# OpenBookReaderv59.net
KiCad netlist of a schematic drawn in EAGLE
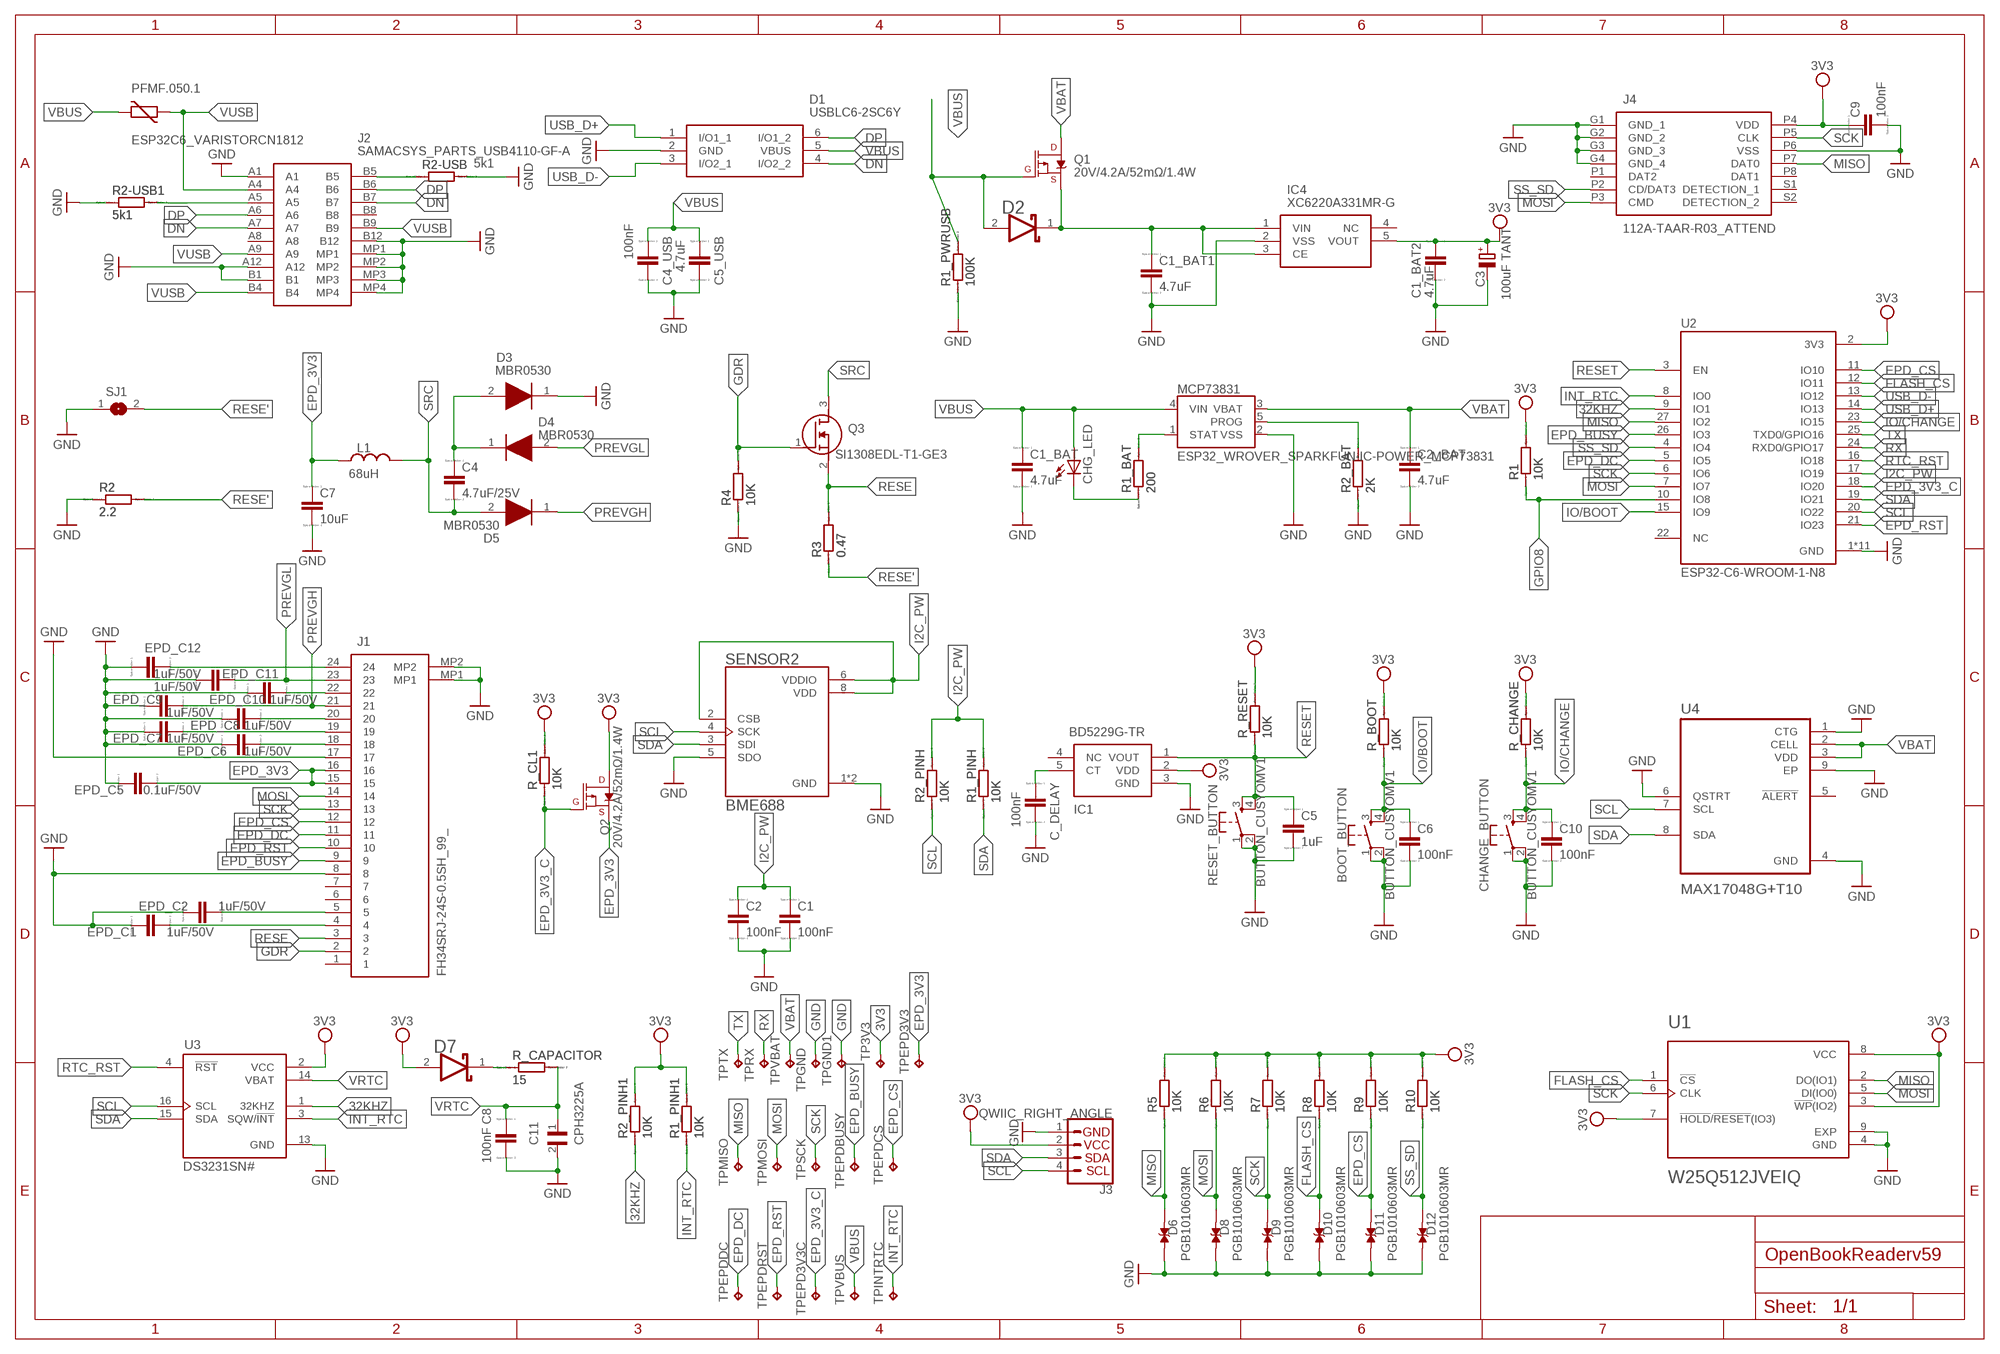
[diagram p0: schematic, sheet 1]

(export (version "E")
  (design (tool "Eeschema 10.0.6"))
  (components
    (comp (ref "BOOT_BUTTON")
      (value "BUTTON_CUSYOMV1")
      (footprint "eagle-import:MYBUTTON")
      (libsource (lib "eagle-import") (part "BUTTON_CUSYOMV1"))
    )
    (comp (ref "C1")
      (value "100nF")
      (footprint "eagle-import:EAGLE-LTSPICE_C0402")
      (libsource (lib "eagle-import") (part "EAGLE-LTSPICE_CC0402"))
    )
    (comp (ref "C1_BAT")
      (value "4.7uF")
      (footprint "eagle-import:EAGLE-LTSPICE_C0402")
      (libsource (lib "eagle-import") (part "EAGLE-LTSPICE_CC0402"))
    )
    (comp (ref "C1_BAT1")
      (value "4.7uF")
      (footprint "eagle-import:EAGLE-LTSPICE_C0402")
      (libsource (lib "eagle-import") (part "EAGLE-LTSPICE_CC0402"))
    )
    (comp (ref "C1_BAT2")
      (value "4.7uF")
      (footprint "eagle-import:EAGLE-LTSPICE_C0402")
      (libsource (lib "eagle-import") (part "EAGLE-LTSPICE_CC0402"))
    )
    (comp (ref "C2")
      (value "100nF")
      (footprint "eagle-import:EAGLE-LTSPICE_C0402")
      (libsource (lib "eagle-import") (part "EAGLE-LTSPICE_CC0402"))
    )
    (comp (ref "C2_BAT")
      (value "4.7uF")
      (footprint "eagle-import:EAGLE-LTSPICE_C0402")
      (libsource (lib "eagle-import") (part "EAGLE-LTSPICE_CC0402"))
    )
    (comp (ref "C3")
      (value "100uF TANT")
      (footprint "eagle-import:RCL_CT3528")
      (libsource (lib "eagle-import") (part "RCL_CPOL-EUCT3528"))
    )
    (comp (ref "C4")
      (value "4.7uF/25V")
      (footprint "eagle-import:EAGLE-LTSPICE_C0402")
      (libsource (lib "eagle-import") (part "EAGLE-LTSPICE_CC0402"))
    )
    (comp (ref "C4_USB")
      (value "100nF")
      (footprint "eagle-import:EAGLE-LTSPICE_C0402")
      (libsource (lib "eagle-import") (part "EAGLE-LTSPICE_CC0402"))
    )
    (comp (ref "C5")
      (value "1uF")
      (footprint "eagle-import:EAGLE-LTSPICE_C0402")
      (libsource (lib "eagle-import") (part "EAGLE-LTSPICE_CC0402"))
    )
    (comp (ref "C5_USB")
      (value "4.7uF")
      (footprint "eagle-import:EAGLE-LTSPICE_C0402")
      (libsource (lib "eagle-import") (part "EAGLE-LTSPICE_CC0402"))
    )
    (comp (ref "C6")
      (value "100nF")
      (footprint "eagle-import:EAGLE-LTSPICE_C0402")
      (libsource (lib "eagle-import") (part "EAGLE-LTSPICE_CC0402"))
    )
    (comp (ref "C7")
      (value "10uF")
      (footprint "eagle-import:EAGLE-LTSPICE_C0402")
      (libsource (lib "eagle-import") (part "EAGLE-LTSPICE_CC0402"))
    )
    (comp (ref "C8")
      (value "100nF")
      (footprint "eagle-import:EAGLE-LTSPICE_C0402")
      (libsource (lib "eagle-import") (part "EAGLE-LTSPICE_CC0402"))
    )
    (comp (ref "C9")
      (value "100nF")
      (footprint "eagle-import:EAGLE-LTSPICE_C0402")
      (libsource (lib "eagle-import") (part "EAGLE-LTSPICE_CC0402"))
    )
    (comp (ref "C10")
      (value "100nF")
      (footprint "eagle-import:EAGLE-LTSPICE_C0402")
      (libsource (lib "eagle-import") (part "EAGLE-LTSPICE_CC0402"))
    )
    (comp (ref "C11")
      (value "CPH3225A")
      (footprint "eagle-import:CAPCP3225X100N")
      (fields (field (name "MF") "Seiko Instruments"))
      (libsource (lib "eagle-import") (part "CPH3225A"))
    )
    (comp (ref "CHANGE_BUTTON")
      (value "BUTTON_CUSYOMV1")
      (footprint "eagle-import:MYBUTTON")
      (libsource (lib "eagle-import") (part "BUTTON_CUSYOMV1"))
    )
    (comp (ref "CHG_LED")
      (value "ADAFRUIT_LEDCHIP-LED0603")
      (footprint "eagle-import:ADAFRUIT_CHIP-LED0603")
      (libsource (lib "eagle-import") (part "ADAFRUIT_LEDCHIP-LED0603"))
    )
    (comp (ref "C_DELAY")
      (value "100nF")
      (footprint "eagle-import:EAGLE-LTSPICE_C0402")
      (libsource (lib "eagle-import") (part "EAGLE-LTSPICE_CC0402"))
    )
    (comp (ref "D1")
      (value "USBLC6-2SC6Y")
      (footprint "eagle-import:SOT95P280X145-6N")
      (fields (field (name "MF") "STMicroelectronics"))
      (libsource (lib "eagle-import") (part "USBLC6-2SC6Y"))
    )
    (comp (ref "D2")
      (value "ESP32_WROVER_AVX---SD0805S020S1R0_AVX_SD0805S020S1R0_0_0AVX_SD0805S020S1R0_0_0")
      (footprint "eagle-import:ESP32_WROVER_AVX---SD0805S020S1R0_AVX_SD0805S020S1R0_0")
      (fields
        (field (name "DIGIKEY_PART_NUMBER") "478-7800-1-ND")
        (field (name "MF") "AVX")
        (field (name "MOUSER_PART_NUMBER") "581-SD0805S020S1R0")
      )
      (libsource (lib "eagle-import") (part "ESP32_WROVER_AVX---SD0805S020S1R0_AVX_SD0805S020S1R0_0_0AVX_SD0805S020S1R0_0_0"))
    )
    (comp (ref "D3")
      (value "MBR0530")
      (footprint "eagle-import:SOD3716X135N")
      (fields (field (name "MF") "ON Semiconductor"))
      (libsource (lib "eagle-import") (part "MBR0530"))
    )
    (comp (ref "D4")
      (value "MBR0530")
      (footprint "eagle-import:SOD3716X135N")
      (fields (field (name "MF") "ON Semiconductor"))
      (libsource (lib "eagle-import") (part "MBR0530"))
    )
    (comp (ref "D5")
      (value "MBR0530")
      (footprint "eagle-import:SOD3716X135N")
      (fields (field (name "MF") "ON Semiconductor"))
      (libsource (lib "eagle-import") (part "MBR0530"))
    )
    (comp (ref "D6")
      (value "PGB1010603MR")
      (footprint "eagle-import:DIOC1608X36N")
      (fields (field (name "MF") "Littelfuse Inc."))
      (libsource (lib "eagle-import") (part "PGB1010603MR"))
    )
    (comp (ref "D7")
      (value "ESP32_WROVER_AVX---SD0805S020S1R0_AVX_SD0805S020S1R0_0_0AVX_SD0805S020S1R0_0_0")
      (footprint "eagle-import:ESP32_WROVER_AVX---SD0805S020S1R0_AVX_SD0805S020S1R0_0")
      (fields
        (field (name "DIGIKEY_PART_NUMBER") "478-7800-1-ND")
        (field (name "MF") "AVX")
        (field (name "MOUSER_PART_NUMBER") "581-SD0805S020S1R0")
      )
      (libsource (lib "eagle-import") (part "ESP32_WROVER_AVX---SD0805S020S1R0_AVX_SD0805S020S1R0_0_0AVX_SD0805S020S1R0_0_0"))
    )
    (comp (ref "D8")
      (value "PGB1010603MR")
      (footprint "eagle-import:DIOC1608X36N")
      (fields (field (name "MF") "Littelfuse Inc."))
      (libsource (lib "eagle-import") (part "PGB1010603MR"))
    )
    (comp (ref "D9")
      (value "PGB1010603MR")
      (footprint "eagle-import:DIOC1608X36N")
      (fields (field (name "MF") "Littelfuse Inc."))
      (libsource (lib "eagle-import") (part "PGB1010603MR"))
    )
    (comp (ref "D10")
      (value "PGB1010603MR")
      (footprint "eagle-import:DIOC1608X36N")
      (fields (field (name "MF") "Littelfuse Inc."))
      (libsource (lib "eagle-import") (part "PGB1010603MR"))
    )
    (comp (ref "D11")
      (value "PGB1010603MR")
      (footprint "eagle-import:DIOC1608X36N")
      (fields (field (name "MF") "Littelfuse Inc."))
      (libsource (lib "eagle-import") (part "PGB1010603MR"))
    )
    (comp (ref "D12")
      (value "PGB1010603MR")
      (footprint "eagle-import:DIOC1608X36N")
      (fields (field (name "MF") "Littelfuse Inc."))
      (libsource (lib "eagle-import") (part "PGB1010603MR"))
    )
    (comp (ref "EPD_C1")
      (value "1uF/50V")
      (footprint "eagle-import:EAGLE-LTSPICE_C0402")
      (libsource (lib "eagle-import") (part "EAGLE-LTSPICE_CC0402"))
    )
    (comp (ref "EPD_C2")
      (value "1uF/50V")
      (footprint "eagle-import:EAGLE-LTSPICE_C0402")
      (libsource (lib "eagle-import") (part "EAGLE-LTSPICE_CC0402"))
    )
    (comp (ref "EPD_C5")
      (value "0.1uF/50V")
      (footprint "eagle-import:EAGLE-LTSPICE_C0402")
      (libsource (lib "eagle-import") (part "EAGLE-LTSPICE_CC0402"))
    )
    (comp (ref "EPD_C6")
      (value "1uF/50V")
      (footprint "eagle-import:EAGLE-LTSPICE_C0402")
      (libsource (lib "eagle-import") (part "EAGLE-LTSPICE_CC0402"))
    )
    (comp (ref "EPD_C7")
      (value "1uF/50V")
      (footprint "eagle-import:EAGLE-LTSPICE_C0402")
      (libsource (lib "eagle-import") (part "EAGLE-LTSPICE_CC0402"))
    )
    (comp (ref "EPD_C8")
      (value "1uF/50V")
      (footprint "eagle-import:EAGLE-LTSPICE_C0402")
      (libsource (lib "eagle-import") (part "EAGLE-LTSPICE_CC0402"))
    )
    (comp (ref "EPD_C9")
      (value "1uF/50V")
      (footprint "eagle-import:EAGLE-LTSPICE_C0402")
      (libsource (lib "eagle-import") (part "EAGLE-LTSPICE_CC0402"))
    )
    (comp (ref "EPD_C10")
      (value "1uF/50V")
      (footprint "eagle-import:EAGLE-LTSPICE_C0402")
      (libsource (lib "eagle-import") (part "EAGLE-LTSPICE_CC0402"))
    )
    (comp (ref "EPD_C11")
      (value "1uF/50V")
      (footprint "eagle-import:EAGLE-LTSPICE_C0402")
      (libsource (lib "eagle-import") (part "EAGLE-LTSPICE_CC0402"))
    )
    (comp (ref "EPD_C12")
      (value "1uF/50V")
      (footprint "eagle-import:EAGLE-LTSPICE_C0402")
      (libsource (lib "eagle-import") (part "EAGLE-LTSPICE_CC0402"))
    )
    (comp (ref "IC1")
      (value "BD5229G-TR")
      (footprint "eagle-import:SOT95P280X125-5N")
      (fields (field (name "MOUSER_PART_NUMBER") "755-BD5229G-TR"))
      (libsource (lib "eagle-import") (part "BD5229G-TR"))
    )
    (comp (ref "IC4")
      (value "XC6220A331MR-G")
      (footprint "eagle-import:SOT95P280X120-5N")
      (fields (field (name "MOUSER_PART_NUMBER") "865-XC6220A331MR-G"))
      (libsource (lib "eagle-import") (part "XC6220A331MR-G"))
    )
    (comp (ref "J1")
      (value "FH34SRJ-24S-0.5SH_99_")
      (footprint "eagle-import:FH34SRJ24S05SH99")
      (fields
        (field (name "MANUFACTURER_PART_NUMBER") "FH34SRJ-24S-0.5SH(99)")
        (field (name "MOUSER_PART_NUMBER") "798-FH34SRJ24S05SH99")
      )
      (libsource (lib "eagle-import") (part "FH34SRJ-24S-0.5SH_99_"))
    )
    (comp (ref "J2")
      (value "SAMACSYS_PARTS_USB4110-GF-A")
      (footprint "eagle-import:SAMACSYS_PARTS_USB4110GFA")
      (fields
        (field (name "MANUFACTURER_PART_NUMBER") "USB4110-GF-A")
        (field (name "MOUSER_PART_NUMBER") "640-USB4110-GF-A")
      )
      (libsource (lib "eagle-import") (part "SAMACSYS_PARTS_USB4110-GF-A"))
    )
    (comp (ref "J3")
      (value "QWIIC_RIGHT_ANGLE")
      (footprint "eagle-import:JST04_1MM_RA")
      (libsource (lib "eagle-import") (part "QWIIC_CONNECTORJS-1MM"))
    )
    (comp (ref "J4")
      (value "112A-TAAR-R03_ATTEND")
      (footprint "eagle-import:112ATAARR03ATTEND")
      (fields (field (name "MANUFACTURER_PART_NUMBER") "112A-TAAR-R03 ATTEND"))
      (libsource (lib "eagle-import") (part "112A-TAAR-R03_ATTEND"))
    )
    (comp (ref "L1")
      (value "68uH")
      (footprint "eagle-import:INDC1006X60N")
      (libsource (lib "eagle-import") (part "INDUCTORCHIP-0402(1006-METRIC)_"))
    )
    (comp (ref "MCP73831")
      (value "ESP32_WROVER_SPARKFUN-IC-POWER_MCP73831")
      (footprint "eagle-import:ESP32_WROVER_SPARKFUN-IC-POWER_SOT23-5")
      (libsource (lib "eagle-import") (part "ESP32_WROVER_SPARKFUN-IC-POWER_MCP73831"))
    )
    (comp (ref "PFMF.050.1")
      (value "ESP32C6_VARISTORCN1812")
      (footprint "eagle-import:ESP32C6_VARISTOR_CT_CN1812")
      (libsource (lib "eagle-import") (part "ESP32C6_VARISTORCN1812"))
    )
    (comp (ref "Q1")
      (value "20V/4.2A/52mΩ/1.4W")
      (footprint "eagle-import:ESP32_WROVER_SPARKFUN-DISCRETESEMI_SOT23-3")
      (libsource (lib "eagle-import") (part "ESP32_WROVER_SPARKFUN-DISCRETESEMI_MOSFET_PCH-DMG2305UX-7"))
    )
    (comp (ref "Q2")
      (value "20V/4.2A/52mΩ/1.4W")
      (footprint "eagle-import:ESP32_WROVER_SPARKFUN-DISCRETESEMI_SOT23-3")
      (libsource (lib "eagle-import") (part "ESP32_WROVER_SPARKFUN-DISCRETESEMI_MOSFET_PCH-DMG2305UX-7"))
    )
    (comp (ref "Q3")
      (value "SI1308EDL-T1-GE3")
      (footprint "eagle-import:SOT65P210X110-3N")
      (fields (field (name "MF") "Vishay Siliconix"))
      (libsource (lib "eagle-import") (part "SI1308EDL-T1-GE3"))
    )
    (comp (ref "R1")
      (value "10K")
      (footprint "eagle-import:ESP32_WROVER_EAGLE-LTSPICE_R0402")
      (libsource (lib "eagle-import") (part "ESP32_WROVER_EAGLE-LTSPICE_RR0402"))
    )
    (comp (ref "R1_BAT")
      (value "200")
      (footprint "eagle-import:ESP32_WROVER_EAGLE-LTSPICE_R0402")
      (libsource (lib "eagle-import") (part "ESP32_WROVER_EAGLE-LTSPICE_RR0402"))
    )
    (comp (ref "R1_PINH")
      (value "10K")
      (footprint "eagle-import:ESP32_WROVER_EAGLE-LTSPICE_R0402")
      (libsource (lib "eagle-import") (part "ESP32_WROVER_EAGLE-LTSPICE_RR0402"))
    )
    (comp (ref "R1_PINH1")
      (value "10K")
      (footprint "eagle-import:ESP32_WROVER_EAGLE-LTSPICE_R0402")
      (libsource (lib "eagle-import") (part "ESP32_WROVER_EAGLE-LTSPICE_RR0402"))
    )
    (comp (ref "R1_PWRUSB")
      (value "100K")
      (footprint "eagle-import:ESP32_WROVER_EAGLE-LTSPICE_R0402")
      (libsource (lib "eagle-import") (part "ESP32_WROVER_EAGLE-LTSPICE_RR0402"))
    )
    (comp (ref "R2")
      (value "2.2")
      (footprint "eagle-import:ESP32_WROVER_EAGLE-LTSPICE_R0402")
      (libsource (lib "eagle-import") (part "ESP32_WROVER_EAGLE-LTSPICE_RR0402"))
    )
    (comp (ref "R2-USB")
      (value "5k1")
      (footprint "eagle-import:ESP32_WROVER_EAGLE-LTSPICE_R0402")
      (libsource (lib "eagle-import") (part "ESP32_WROVER_EAGLE-LTSPICE_RR0402"))
    )
    (comp (ref "R2-USB1")
      (value "5k1")
      (footprint "eagle-import:ESP32_WROVER_EAGLE-LTSPICE_R0402")
      (libsource (lib "eagle-import") (part "ESP32_WROVER_EAGLE-LTSPICE_RR0402"))
    )
    (comp (ref "R2_BAT")
      (value "2K")
      (footprint "eagle-import:ESP32_WROVER_EAGLE-LTSPICE_R0402")
      (libsource (lib "eagle-import") (part "ESP32_WROVER_EAGLE-LTSPICE_RR0402"))
    )
    (comp (ref "R2_PINH")
      (value "10K")
      (footprint "eagle-import:ESP32_WROVER_EAGLE-LTSPICE_R0402")
      (libsource (lib "eagle-import") (part "ESP32_WROVER_EAGLE-LTSPICE_RR0402"))
    )
    (comp (ref "R2_PINH1")
      (value "10K")
      (footprint "eagle-import:ESP32_WROVER_EAGLE-LTSPICE_R0402")
      (libsource (lib "eagle-import") (part "ESP32_WROVER_EAGLE-LTSPICE_RR0402"))
    )
    (comp (ref "R3")
      (value "0.47")
      (footprint "eagle-import:ESP32_WROVER_EAGLE-LTSPICE_R0402")
      (libsource (lib "eagle-import") (part "ESP32_WROVER_EAGLE-LTSPICE_RR0402"))
    )
    (comp (ref "R4")
      (value "10K")
      (footprint "eagle-import:ESP32_WROVER_EAGLE-LTSPICE_R0402")
      (libsource (lib "eagle-import") (part "ESP32_WROVER_EAGLE-LTSPICE_RR0402"))
    )
    (comp (ref "R5")
      (value "10K")
      (footprint "eagle-import:ESP32_WROVER_EAGLE-LTSPICE_R0402")
      (libsource (lib "eagle-import") (part "ESP32_WROVER_EAGLE-LTSPICE_RR0402"))
    )
    (comp (ref "R6")
      (value "10K")
      (footprint "eagle-import:ESP32_WROVER_EAGLE-LTSPICE_R0402")
      (libsource (lib "eagle-import") (part "ESP32_WROVER_EAGLE-LTSPICE_RR0402"))
    )
    (comp (ref "R7")
      (value "10K")
      (footprint "eagle-import:ESP32_WROVER_EAGLE-LTSPICE_R0402")
      (libsource (lib "eagle-import") (part "ESP32_WROVER_EAGLE-LTSPICE_RR0402"))
    )
    (comp (ref "R8")
      (value "10K")
      (footprint "eagle-import:ESP32_WROVER_EAGLE-LTSPICE_R0402")
      (libsource (lib "eagle-import") (part "ESP32_WROVER_EAGLE-LTSPICE_RR0402"))
    )
    (comp (ref "R9")
      (value "10K")
      (footprint "eagle-import:ESP32_WROVER_EAGLE-LTSPICE_R0402")
      (libsource (lib "eagle-import") (part "ESP32_WROVER_EAGLE-LTSPICE_RR0402"))
    )
    (comp (ref "R10")
      (value "10K")
      (footprint "eagle-import:ESP32_WROVER_EAGLE-LTSPICE_R0402")
      (libsource (lib "eagle-import") (part "ESP32_WROVER_EAGLE-LTSPICE_RR0402"))
    )
    (comp (ref "RESET_BUTTON")
      (value "BUTTON_CUSYOMV1")
      (footprint "eagle-import:MYBUTTON")
      (libsource (lib "eagle-import") (part "BUTTON_CUSYOMV1"))
    )
    (comp (ref "R_BOOT")
      (value "10K")
      (footprint "eagle-import:ESP32_WROVER_EAGLE-LTSPICE_R0402")
      (libsource (lib "eagle-import") (part "ESP32_WROVER_EAGLE-LTSPICE_RR0402"))
    )
    (comp (ref "R_CAPACITOR")
      (value "15")
      (footprint "eagle-import:ESP32_WROVER_EAGLE-LTSPICE_R0402")
      (libsource (lib "eagle-import") (part "ESP32_WROVER_EAGLE-LTSPICE_RR0402"))
    )
    (comp (ref "R_CHANGE")
      (value "10K")
      (footprint "eagle-import:ESP32_WROVER_EAGLE-LTSPICE_R0402")
      (libsource (lib "eagle-import") (part "ESP32_WROVER_EAGLE-LTSPICE_RR0402"))
    )
    (comp (ref "R_CL1")
      (value "10K")
      (footprint "eagle-import:ESP32_WROVER_EAGLE-LTSPICE_R0402")
      (libsource (lib "eagle-import") (part "ESP32_WROVER_EAGLE-LTSPICE_RR0402"))
    )
    (comp (ref "R_RESET")
      (value "10K")
      (footprint "eagle-import:ESP32_WROVER_EAGLE-LTSPICE_R0402")
      (libsource (lib "eagle-import") (part "ESP32_WROVER_EAGLE-LTSPICE_RR0402"))
    )
    (comp (ref "SENSOR2")
      (value "BME688")
      (footprint "eagle-import:ESP32_WROVER_BME680_PSON80P300X300X100-8N")
      (fields (field (name "MF") "Bosch Sensortec") (field (name "MP") "BME680"))
      (libsource (lib "eagle-import") (part "ESP32_WROVER_BME680_BME680"))
    )
    (comp (ref "SJ1") (value "SJ") (footprint "eagle-import:SJ") (libsource (lib "eagle-import") (part "SJ")))
    (comp (ref "TP3V3")
      (value "TPTP20R")
      (footprint "eagle-import:TP20R")
      (libsource (lib "eagle-import") (part "TPTP20R"))
    )
    (comp (ref "TPEPD3V3")
      (value "TPTP20R")
      (footprint "eagle-import:TP20R")
      (libsource (lib "eagle-import") (part "TPTP20R"))
    )
    (comp (ref "TPEPD3V3C")
      (value "TPTP20R")
      (footprint "eagle-import:TP20R")
      (libsource (lib "eagle-import") (part "TPTP20R"))
    )
    (comp (ref "TPEPDBUSY")
      (value "TPTP20R")
      (footprint "eagle-import:TP20R")
      (libsource (lib "eagle-import") (part "TPTP20R"))
    )
    (comp (ref "TPEPDCS")
      (value "TPTP20R")
      (footprint "eagle-import:TP20R")
      (libsource (lib "eagle-import") (part "TPTP20R"))
    )
    (comp (ref "TPEPDDC")
      (value "TPTP20R")
      (footprint "eagle-import:TP20R")
      (libsource (lib "eagle-import") (part "TPTP20R"))
    )
    (comp (ref "TPEPDRST")
      (value "TPTP20R")
      (footprint "eagle-import:TP20R")
      (libsource (lib "eagle-import") (part "TPTP20R"))
    )
    (comp (ref "TPGND")
      (value "TPTP20R")
      (footprint "eagle-import:TP20R")
      (libsource (lib "eagle-import") (part "TPTP20R"))
    )
    (comp (ref "TPGND1")
      (value "TPTP20R")
      (footprint "eagle-import:TP20R")
      (libsource (lib "eagle-import") (part "TPTP20R"))
    )
    (comp (ref "TPINTRTC")
      (value "TPTP20R")
      (footprint "eagle-import:TP20R")
      (libsource (lib "eagle-import") (part "TPTP20R"))
    )
    (comp (ref "TPMISO")
      (value "TPTP20R")
      (footprint "eagle-import:TP20R")
      (libsource (lib "eagle-import") (part "TPTP20R"))
    )
    (comp (ref "TPMOSI")
      (value "TPTP20R")
      (footprint "eagle-import:TP20R")
      (libsource (lib "eagle-import") (part "TPTP20R"))
    )
    (comp (ref "TPRX")
      (value "TPTP20R")
      (footprint "eagle-import:TP20R")
      (libsource (lib "eagle-import") (part "TPTP20R"))
    )
    (comp (ref "TPSCK")
      (value "TPTP20R")
      (footprint "eagle-import:TP20R")
      (libsource (lib "eagle-import") (part "TPTP20R"))
    )
    (comp (ref "TPTX")
      (value "TPTP20R")
      (footprint "eagle-import:TP20R")
      (libsource (lib "eagle-import") (part "TPTP20R"))
    )
    (comp (ref "TPVBAT")
      (value "TPTP20R")
      (footprint "eagle-import:TP20R")
      (libsource (lib "eagle-import") (part "TPTP20R"))
    )
    (comp (ref "TPVBUS")
      (value "TPTP20R")
      (footprint "eagle-import:TP20R")
      (libsource (lib "eagle-import") (part "TPTP20R"))
    )
    (comp (ref "U1")
      (value "W25Q512JVEIQ")
      (footprint "eagle-import:SON127P600X800X80-9N")
      (fields (field (name "MF") "Winbond Electronics"))
      (libsource (lib "eagle-import") (part "W25Q512JVEIQ"))
    )
    (comp (ref "U2")
      (value "ESP32-C6-WROOM-1-N8")
      (footprint "eagle-import:XCVR_ESP32-C6-WROOM-1-N8")
      (fields (field (name "MF") "Espressif Systems"))
      (libsource (lib "eagle-import") (part "ESP32-C6-WROOM-1-N8"))
    )
    (comp (ref "U3")
      (value "DS3231SN#")
      (footprint "eagle-import:SOIC127P1032X265-16N")
      (fields (field (name "MF") "Analog Devices"))
      (libsource (lib "eagle-import") (part "DS3231SN#"))
    )
    (comp (ref "U4")
      (value "MAX17048G+T10")
      (footprint "eagle-import:SON50P200X200X80-9N")
      (fields (field (name "MF") "Analog Devices"))
      (libsource (lib "eagle-import") (part "MAX17048G+T10"))
    )
  )
  (nets
    (net (code "1") (name "3V3") (class "Default")
      (node (ref "C1_BAT2") (pin "1") (pinfunction "1_1") (pintype "passive"))
      (node (ref "C3") (pin "+") (pinfunction "+_+") (pintype "passive"))
      (node (ref "C9") (pin "1") (pinfunction "1_1") (pintype "passive"))
      (node (ref "D7") (pin "2") (pinfunction "ANODE_2") (pintype "bidirectional"))
      (node (ref "IC1") (pin "2") (pinfunction "VDD_2") (pintype "bidirectional"))
      (node (ref "IC4") (pin "5") (pinfunction "VOUT_5") (pintype "bidirectional"))
      (node (ref "J3") (pin "2") (pinfunction "2_2") (pintype "power_in"))
      (node (ref "J4") (pin "P4") (pinfunction "VDD_P4") (pintype "bidirectional"))
      (node (ref "Q2") (pin "3") (pinfunction "D_3") (pintype "bidirectional"))
      (node (ref "R1") (pin "2") (pinfunction "2_2") (pintype "passive"))
      (node (ref "R10") (pin "2") (pinfunction "2_2") (pintype "passive"))
      (node (ref "R1_PINH1") (pin "2") (pinfunction "2_2") (pintype "passive"))
      (node (ref "R2_PINH1") (pin "2") (pinfunction "2_2") (pintype "passive"))
      (node (ref "R5") (pin "2") (pinfunction "2_2") (pintype "passive"))
      (node (ref "R6") (pin "2") (pinfunction "2_2") (pintype "passive"))
      (node (ref "R7") (pin "2") (pinfunction "2_2") (pintype "passive"))
      (node (ref "R8") (pin "2") (pinfunction "2_2") (pintype "passive"))
      (node (ref "R9") (pin "2") (pinfunction "2_2") (pintype "passive"))
      (node (ref "R_BOOT") (pin "2") (pinfunction "2_2") (pintype "passive"))
      (node (ref "R_CHANGE") (pin "2") (pinfunction "2_2") (pintype "passive"))
      (node (ref "R_CL1") (pin "2") (pinfunction "2_2") (pintype "passive"))
      (node (ref "R_RESET") (pin "2") (pinfunction "2_2") (pintype "passive"))
      (node (ref "TP3V3") (pin "TP") (pinfunction "TP_TP") (pintype "input"))
      (node (ref "U1") (pin "3") (pinfunction "~{WP}(IO2)_3") (pintype "bidirectional"))
      (node (ref "U1") (pin "7") (pinfunction "~{HOLD}/~{RESET}(IO3)_7") (pintype "bidirectional"))
      (node (ref "U1") (pin "8") (pinfunction "VCC_8") (pintype "power_in"))
      (node (ref "U2") (pin "2") (pinfunction "3V3_2") (pintype "power_in"))
      (node (ref "U3") (pin "2") (pinfunction "VCC_2") (pintype "power_in"))
    )
    (net (code "2") (name "32KHZ") (class "Default")
      (node (ref "R2_PINH1") (pin "1") (pinfunction "1_1") (pintype "passive"))
      (node (ref "U2") (pin "9") (pinfunction "IO1_9") (pintype "bidirectional"))
      (node (ref "U3") (pin "1") (pinfunction "32KHZ_1") (pintype "output"))
    )
    (net (code "3") (name "DN") (class "Default")
      (node (ref "D1") (pin "4") (pinfunction "I/O2_2_4") (pintype "bidirectional"))
      (node (ref "J2") (pin "A7") (pinfunction "A7_A7") (pintype "bidirectional"))
      (node (ref "J2") (pin "B7") (pinfunction "B7_B7") (pintype "bidirectional"))
    )
    (net (code "4") (name "DP") (class "Default")
      (node (ref "D1") (pin "6") (pinfunction "I/O1_2_6") (pintype "bidirectional"))
      (node (ref "J2") (pin "A6") (pinfunction "A6_A6") (pintype "bidirectional"))
      (node (ref "J2") (pin "B6") (pinfunction "B6_B6") (pintype "bidirectional"))
    )
    (net (code "5") (name "EPD_3V3") (class "Default")
      (node (ref "C7") (pin "1") (pinfunction "1_1") (pintype "passive"))
      (node (ref "EPD_C5") (pin "2") (pinfunction "2_2") (pintype "passive"))
      (node (ref "J1") (pin "15") (pinfunction "15_15") (pintype "bidirectional"))
      (node (ref "J1") (pin "16") (pinfunction "16_16") (pintype "bidirectional"))
      (node (ref "L1") (pin "1") (pinfunction "1_1") (pintype "passive"))
      (node (ref "Q2") (pin "2") (pinfunction "S_2") (pintype "bidirectional"))
      (node (ref "TPEPD3V3") (pin "TP") (pinfunction "TP_TP") (pintype "input"))
    )
    (net (code "6") (name "EPD_3V3_C") (class "Default")
      (node (ref "Q2") (pin "1") (pinfunction "G_1") (pintype "bidirectional"))
      (node (ref "R_CL1") (pin "1") (pinfunction "1_1") (pintype "passive"))
      (node (ref "TPEPD3V3C") (pin "TP") (pinfunction "TP_TP") (pintype "input"))
      (node (ref "U2") (pin "18") (pinfunction "IO20_18") (pintype "bidirectional"))
    )
    (net (code "7") (name "EPD_BUSY") (class "Default")
      (node (ref "J1") (pin "9") (pinfunction "9_9") (pintype "bidirectional"))
      (node (ref "TPEPDBUSY") (pin "TP") (pinfunction "TP_TP") (pintype "input"))
      (node (ref "U2") (pin "26") (pinfunction "IO3_26") (pintype "bidirectional"))
    )
    (net (code "8") (name "EPD_CS") (class "Default")
      (node (ref "D11") (pin "2") (pinfunction "2_2") (pintype "passive"))
      (node (ref "J1") (pin "12") (pinfunction "12_12") (pintype "bidirectional"))
      (node (ref "R9") (pin "1") (pinfunction "1_1") (pintype "passive"))
      (node (ref "TPEPDCS") (pin "TP") (pinfunction "TP_TP") (pintype "input"))
      (node (ref "U2") (pin "11") (pinfunction "IO10_11") (pintype "bidirectional"))
    )
    (net (code "9") (name "EPD_DC") (class "Default")
      (node (ref "J1") (pin "11") (pinfunction "11_11") (pintype "bidirectional"))
      (node (ref "TPEPDDC") (pin "TP") (pinfunction "TP_TP") (pintype "input"))
      (node (ref "U2") (pin "5") (pinfunction "IO5_5") (pintype "bidirectional"))
    )
    (net (code "10") (name "EPD_RST") (class "Default")
      (node (ref "J1") (pin "10") (pinfunction "10_10") (pintype "bidirectional"))
      (node (ref "TPEPDRST") (pin "TP") (pinfunction "TP_TP") (pintype "input"))
      (node (ref "U2") (pin "21") (pinfunction "IO23_21") (pintype "bidirectional"))
    )
    (net (code "11") (name "FLASH_CS") (class "Default")
      (node (ref "D10") (pin "2") (pinfunction "2_2") (pintype "passive"))
      (node (ref "R8") (pin "1") (pinfunction "1_1") (pintype "passive"))
      (node (ref "U1") (pin "1") (pinfunction "~{CS}_1") (pintype "input"))
      (node (ref "U2") (pin "12") (pinfunction "IO11_12") (pintype "bidirectional"))
    )
    (net (code "12") (name "GDR") (class "Default")
      (node (ref "J1") (pin "2") (pinfunction "2_2") (pintype "bidirectional"))
      (node (ref "Q3") (pin "1") (pinfunction "G_1") (pintype "bidirectional"))
      (node (ref "R4") (pin "2") (pinfunction "2_2") (pintype "passive"))
    )
    (net (code "13") (name "GND") (class "Default")
      (node (ref "BOOT_BUTTON") (pin "1") (pinfunction "1_1") (pintype "passive"))
      (node (ref "BOOT_BUTTON") (pin "2") (pinfunction "2_2") (pintype "passive"))
      (node (ref "C1") (pin "2") (pinfunction "2_2") (pintype "passive"))
      (node (ref "C10") (pin "2") (pinfunction "2_2") (pintype "passive"))
      (node (ref "C11") (pin "2") (pinfunction "2_2") (pintype "passive"))
      (node (ref "C1_BAT") (pin "2") (pinfunction "2_2") (pintype "passive"))
      (node (ref "C1_BAT1") (pin "2") (pinfunction "2_2") (pintype "passive"))
      (node (ref "C1_BAT2") (pin "2") (pinfunction "2_2") (pintype "passive"))
      (node (ref "C2") (pin "2") (pinfunction "2_2") (pintype "passive"))
      (node (ref "C2_BAT") (pin "2") (pinfunction "2_2") (pintype "passive"))
      (node (ref "C3") (pin "-") (pinfunction "-_-") (pintype "passive"))
      (node (ref "C4_USB") (pin "2") (pinfunction "2_2") (pintype "passive"))
      (node (ref "C5") (pin "2") (pinfunction "2_2") (pintype "passive"))
      (node (ref "C5_USB") (pin "2") (pinfunction "2_2") (pintype "passive"))
      (node (ref "C6") (pin "2") (pinfunction "2_2") (pintype "passive"))
      (node (ref "C7") (pin "2") (pinfunction "2_2") (pintype "passive"))
      (node (ref "C8") (pin "2") (pinfunction "2_2") (pintype "passive"))
      (node (ref "C9") (pin "2") (pinfunction "2_2") (pintype "passive"))
      (node (ref "CHANGE_BUTTON") (pin "1") (pinfunction "1_1") (pintype "passive"))
      (node (ref "CHANGE_BUTTON") (pin "2") (pinfunction "2_2") (pintype "passive"))
      (node (ref "C_DELAY") (pin "2") (pinfunction "2_2") (pintype "passive"))
      (node (ref "D1") (pin "2") (pinfunction "GND_2") (pintype "bidirectional"))
      (node (ref "D10") (pin "1") (pinfunction "1_1") (pintype "passive"))
      (node (ref "D11") (pin "1") (pinfunction "1_1") (pintype "passive"))
      (node (ref "D12") (pin "1") (pinfunction "1_1") (pintype "passive"))
      (node (ref "D3") (pin "1") (pinfunction "K_1") (pintype "bidirectional"))
      (node (ref "D6") (pin "1") (pinfunction "1_1") (pintype "passive"))
      (node (ref "D8") (pin "1") (pinfunction "1_1") (pintype "passive"))
      (node (ref "D9") (pin "1") (pinfunction "1_1") (pintype "passive"))
      (node (ref "EPD_C1") (pin "1") (pinfunction "1_1") (pintype "passive"))
      (node (ref "EPD_C10") (pin "1") (pinfunction "1_1") (pintype "passive"))
      (node (ref "EPD_C11") (pin "1") (pinfunction "1_1") (pintype "passive"))
      (node (ref "EPD_C12") (pin "1") (pinfunction "1_1") (pintype "passive"))
      (node (ref "EPD_C2") (pin "1") (pinfunction "1_1") (pintype "passive"))
      (node (ref "EPD_C5") (pin "1") (pinfunction "1_1") (pintype "passive"))
      (node (ref "EPD_C6") (pin "1") (pinfunction "1_1") (pintype "passive"))
      (node (ref "EPD_C7") (pin "1") (pinfunction "1_1") (pintype "passive"))
      (node (ref "EPD_C8") (pin "1") (pinfunction "1_1") (pintype "passive"))
      (node (ref "EPD_C9") (pin "1") (pinfunction "1_1") (pintype "passive"))
      (node (ref "IC1") (pin "3") (pinfunction "GND_3") (pintype "bidirectional"))
      (node (ref "IC4") (pin "2") (pinfunction "VSS_2") (pintype "bidirectional"))
      (node (ref "J1") (pin "17") (pinfunction "17_17") (pintype "bidirectional"))
      (node (ref "J1") (pin "8") (pinfunction "8_8") (pintype "bidirectional"))
      (node (ref "J1") (pin "MP1") (pinfunction "MP1_MP1") (pintype "bidirectional"))
      (node (ref "J1") (pin "MP2") (pinfunction "MP2_MP2") (pintype "bidirectional"))
      (node (ref "J2") (pin "A1") (pinfunction "A1_A1") (pintype "bidirectional"))
      (node (ref "J2") (pin "A12") (pinfunction "A12_A12") (pintype "bidirectional"))
      (node (ref "J2") (pin "B1") (pinfunction "B1_B1") (pintype "bidirectional"))
      (node (ref "J2") (pin "B12") (pinfunction "B12_B12") (pintype "bidirectional"))
      (node (ref "J2") (pin "MP1") (pinfunction "MP1_MP1") (pintype "bidirectional"))
      (node (ref "J2") (pin "MP2") (pinfunction "MP2_MP2") (pintype "bidirectional"))
      (node (ref "J2") (pin "MP3") (pinfunction "MP3_MP3") (pintype "bidirectional"))
      (node (ref "J2") (pin "MP4") (pinfunction "MP4_MP4") (pintype "bidirectional"))
      (node (ref "J3") (pin "1") (pinfunction "1_1") (pintype "power_in"))
      (node (ref "J4") (pin "G1") (pinfunction "GND_1_G1") (pintype "bidirectional"))
      (node (ref "J4") (pin "G2") (pinfunction "GND_2_G2") (pintype "bidirectional"))
      (node (ref "J4") (pin "G3") (pinfunction "GND_3_G3") (pintype "bidirectional"))
      (node (ref "J4") (pin "G4") (pinfunction "GND_4_G4") (pintype "bidirectional"))
      (node (ref "J4") (pin "P6") (pinfunction "VSS_P6") (pintype "bidirectional"))
      (node (ref "MCP73831") (pin "2") (pinfunction "VSS_2") (pintype "power_in"))
      (node (ref "R1_PWRUSB") (pin "1") (pinfunction "1_1") (pintype "passive"))
      (node (ref "R2") (pin "1") (pinfunction "1_1") (pintype "passive"))
      (node (ref "R2-USB") (pin "2") (pinfunction "2_2") (pintype "passive"))
      (node (ref "R2-USB1") (pin "1") (pinfunction "1_1") (pintype "passive"))
      (node (ref "R2_BAT") (pin "1") (pinfunction "1_1") (pintype "passive"))
      (node (ref "R4") (pin "1") (pinfunction "1_1") (pintype "passive"))
      (node (ref "RESET_BUTTON") (pin "1") (pinfunction "1_1") (pintype "passive"))
      (node (ref "RESET_BUTTON") (pin "2") (pinfunction "2_2") (pintype "passive"))
      (node (ref "SENSOR2") (pin "1") (pinfunction "GND_1") (pintype "power_in"))
      (node (ref "SENSOR2") (pin "5") (pinfunction "SDO_5") (pintype "bidirectional"))
      (node (ref "SENSOR2") (pin "7") (pinfunction "GND_7") (pintype "power_in"))
      (node (ref "SJ1") (pin "1") (pinfunction "1_1") (pintype "passive"))
      (node (ref "TPGND") (pin "TP") (pinfunction "TP_TP") (pintype "input"))
      (node (ref "TPGND1") (pin "TP") (pinfunction "TP_TP") (pintype "input"))
      (node (ref "U1") (pin "4") (pinfunction "GND_4") (pintype "power_in"))
      (node (ref "U1") (pin "9") (pinfunction "EXP_9") (pintype "passive"))
      (node (ref "U2") (pin "1") (pinfunction "GND_1") (pintype "power_in"))
      (node (ref "U2") (pin "28") (pinfunction "GND_28") (pintype "power_in"))
      (node (ref "U2") (pin "29_1") (pinfunction "GND_29_1") (pintype "power_in"))
      (node (ref "U2") (pin "29_2") (pinfunction "GND_29_2") (pintype "power_in"))
      (node (ref "U2") (pin "29_3") (pinfunction "GND_29_3") (pintype "power_in"))
      (node (ref "U2") (pin "29_4") (pinfunction "GND_29_4") (pintype "power_in"))
      (node (ref "U2") (pin "29_5") (pinfunction "GND_29_5") (pintype "power_in"))
      (node (ref "U2") (pin "29_6") (pinfunction "GND_29_6") (pintype "power_in"))
      (node (ref "U2") (pin "29_7") (pinfunction "GND_29_7") (pintype "power_in"))
      (node (ref "U2") (pin "29_8") (pinfunction "GND_29_8") (pintype "power_in"))
      (node (ref "U2") (pin "29_9") (pinfunction "GND_29_9") (pintype "power_in"))
      (node (ref "U3") (pin "13") (pinfunction "GND_13") (pintype "power_in"))
      (node (ref "U4") (pin "1") (pinfunction "CTG_1") (pintype "power_in"))
      (node (ref "U4") (pin "4") (pinfunction "GND_4") (pintype "power_in"))
      (node (ref "U4") (pin "6") (pinfunction "QSTRT_6") (pintype "input"))
      (node (ref "U4") (pin "9") (pinfunction "EP_9") (pintype "power_in"))
    )
    (net (code "14") (name "GPIO8") (class "Default")
      (node (ref "R1") (pin "1") (pinfunction "1_1") (pintype "passive"))
      (node (ref "U2") (pin "10") (pinfunction "IO8_10") (pintype "bidirectional"))
    )
    (net (code "15") (name "I2C_PW") (class "Default")
      (node (ref "C1") (pin "1") (pinfunction "1_1") (pintype "passive"))
      (node (ref "C2") (pin "1") (pinfunction "1_1") (pintype "passive"))
      (node (ref "R1_PINH") (pin "2") (pinfunction "2_2") (pintype "passive"))
      (node (ref "R2_PINH") (pin "2") (pinfunction "2_2") (pintype "passive"))
      (node (ref "SENSOR2") (pin "2") (pinfunction "CSB_2") (pintype "input"))
      (node (ref "SENSOR2") (pin "6") (pinfunction "VDDIO_6") (pintype "power_in"))
      (node (ref "SENSOR2") (pin "8") (pinfunction "VDD_8") (pintype "power_in"))
      (node (ref "U2") (pin "17") (pinfunction "IO19_17") (pintype "bidirectional"))
    )
    (net (code "16") (name "INT_RTC") (class "Default")
      (node (ref "R1_PINH1") (pin "1") (pinfunction "1_1") (pintype "passive"))
      (node (ref "TPINTRTC") (pin "TP") (pinfunction "TP_TP") (pintype "input"))
      (node (ref "U2") (pin "8") (pinfunction "IO0_8") (pintype "bidirectional"))
      (node (ref "U3") (pin "3") (pinfunction "SQW/~{INT}_3") (pintype "output"))
    )
    (net (code "17") (name "IO{slash}BOOT") (class "Default")
      (node (ref "BOOT_BUTTON") (pin "3") (pinfunction "3_3") (pintype "passive"))
      (node (ref "BOOT_BUTTON") (pin "4") (pinfunction "4_4") (pintype "passive"))
      (node (ref "C6") (pin "1") (pinfunction "1_1") (pintype "passive"))
      (node (ref "R_BOOT") (pin "1") (pinfunction "1_1") (pintype "passive"))
      (node (ref "U2") (pin "15") (pinfunction "IO9_15") (pintype "bidirectional"))
    )
    (net (code "18") (name "IO{slash}CHANGE") (class "Default")
      (node (ref "C10") (pin "1") (pinfunction "1_1") (pintype "passive"))
      (node (ref "CHANGE_BUTTON") (pin "3") (pinfunction "3_3") (pintype "passive"))
      (node (ref "CHANGE_BUTTON") (pin "4") (pinfunction "4_4") (pintype "passive"))
      (node (ref "R_CHANGE") (pin "1") (pinfunction "1_1") (pintype "passive"))
      (node (ref "U2") (pin "23") (pinfunction "IO15_23") (pintype "bidirectional"))
    )
    (net (code "19") (name "MISO") (class "Default")
      (node (ref "D6") (pin "2") (pinfunction "2_2") (pintype "passive"))
      (node (ref "J4") (pin "P7") (pinfunction "DAT0_P7") (pintype "bidirectional"))
      (node (ref "R5") (pin "1") (pinfunction "1_1") (pintype "passive"))
      (node (ref "TPMISO") (pin "TP") (pinfunction "TP_TP") (pintype "input"))
      (node (ref "U1") (pin "2") (pinfunction "DO(IO1)_2") (pintype "bidirectional"))
      (node (ref "U2") (pin "27") (pinfunction "IO2_27") (pintype "bidirectional"))
    )
    (net (code "20") (name "MOSI") (class "Default")
      (node (ref "D8") (pin "2") (pinfunction "2_2") (pintype "passive"))
      (node (ref "J1") (pin "14") (pinfunction "14_14") (pintype "bidirectional"))
      (node (ref "J4") (pin "P3") (pinfunction "CMD_P3") (pintype "bidirectional"))
      (node (ref "R6") (pin "1") (pinfunction "1_1") (pintype "passive"))
      (node (ref "TPMOSI") (pin "TP") (pinfunction "TP_TP") (pintype "input"))
      (node (ref "U1") (pin "5") (pinfunction "DI(IO0)_5") (pintype "bidirectional"))
      (node (ref "U2") (pin "7") (pinfunction "IO7_7") (pintype "bidirectional"))
    )
    (net (code "21") (name "Net-(CHG_LED-PadC)") (class "Default")
      (node (ref "CHG_LED") (pin "C") (pinfunction "C_C") (pintype "passive"))
      (node (ref "R1_BAT") (pin "1") (pinfunction "1_1") (pintype "passive"))
    )
    (net (code "22") (name "Net-(D2-CATHODE)") (class "Default")
      (node (ref "C1_BAT1") (pin "1") (pinfunction "1_1") (pintype "passive"))
      (node (ref "D2") (pin "1") (pinfunction "CATHODE_1") (pintype "bidirectional"))
      (node (ref "IC4") (pin "1") (pinfunction "VIN_1") (pintype "bidirectional"))
      (node (ref "IC4") (pin "3") (pinfunction "CE_3") (pintype "bidirectional"))
      (node (ref "Q1") (pin "2") (pinfunction "S_2") (pintype "bidirectional"))
    )
    (net (code "23") (name "Net-(D3-A)") (class "Default")
      (node (ref "C4") (pin "1") (pinfunction "1_1") (pintype "passive"))
      (node (ref "D3") (pin "2") (pinfunction "A_2") (pintype "bidirectional"))
      (node (ref "D4") (pin "1") (pinfunction "K_1") (pintype "bidirectional"))
    )
    (net (code "24") (name "Net-(D7-CATHODE)") (class "Default")
      (node (ref "D7") (pin "1") (pinfunction "CATHODE_1") (pintype "bidirectional"))
      (node (ref "R_CAPACITOR") (pin "1") (pinfunction "1_1") (pintype "passive"))
    )
    (net (code "25") (name "Net-(EPD_C1-Pad2)") (class "Default")
      (node (ref "EPD_C1") (pin "2") (pinfunction "2_2") (pintype "passive"))
      (node (ref "J1") (pin "4") (pinfunction "4_4") (pintype "bidirectional"))
    )
    (net (code "26") (name "Net-(EPD_C2-Pad2)") (class "Default")
      (node (ref "EPD_C2") (pin "2") (pinfunction "2_2") (pintype "passive"))
      (node (ref "J1") (pin "5") (pinfunction "5_5") (pintype "bidirectional"))
    )
    (net (code "27") (name "Net-(EPD_C6-Pad2)") (class "Default")
      (node (ref "EPD_C6") (pin "2") (pinfunction "2_2") (pintype "passive"))
      (node (ref "J1") (pin "18") (pinfunction "18_18") (pintype "bidirectional"))
    )
    (net (code "28") (name "Net-(EPD_C7-Pad2)") (class "Default")
      (node (ref "EPD_C7") (pin "2") (pinfunction "2_2") (pintype "passive"))
      (node (ref "J1") (pin "19") (pinfunction "19_19") (pintype "bidirectional"))
    )
    (net (code "29") (name "Net-(EPD_C8-Pad2)") (class "Default")
      (node (ref "EPD_C8") (pin "2") (pinfunction "2_2") (pintype "passive"))
      (node (ref "J1") (pin "20") (pinfunction "20_20") (pintype "bidirectional"))
    )
    (net (code "30") (name "Net-(EPD_C10-Pad2)") (class "Default")
      (node (ref "EPD_C10") (pin "2") (pinfunction "2_2") (pintype "passive"))
      (node (ref "J1") (pin "22") (pinfunction "22_22") (pintype "bidirectional"))
    )
    (net (code "31") (name "Net-(EPD_C12-Pad2)") (class "Default")
      (node (ref "EPD_C12") (pin "2") (pinfunction "2_2") (pintype "passive"))
      (node (ref "J1") (pin "24") (pinfunction "24_24") (pintype "bidirectional"))
    )
    (net (code "32") (name "Net-(IC1-CT)") (class "Default")
      (node (ref "C_DELAY") (pin "1") (pinfunction "1_1") (pintype "passive"))
      (node (ref "IC1") (pin "5") (pinfunction "CT_5") (pintype "bidirectional"))
    )
    (net (code "33") (name "Net-(J2-PadA5)") (class "Default")
      (node (ref "J2") (pin "A5") (pinfunction "A5_A5") (pintype "bidirectional"))
      (node (ref "R2-USB1") (pin "2") (pinfunction "2_2") (pintype "passive"))
    )
    (net (code "34") (name "Net-(J2-PadB5)") (class "Default")
      (node (ref "J2") (pin "B5") (pinfunction "B5_B5") (pintype "bidirectional"))
      (node (ref "R2-USB") (pin "1") (pinfunction "1_1") (pintype "passive"))
    )
    (net (code "35") (name "Net-(MCP73831-PROG)") (class "Default")
      (node (ref "MCP73831") (pin "5") (pinfunction "PROG_5") (pintype "input"))
      (node (ref "R2_BAT") (pin "2") (pinfunction "2_2") (pintype "passive"))
    )
    (net (code "36") (name "Net-(MCP73831-STAT)") (class "Default")
      (node (ref "MCP73831") (pin "1") (pinfunction "STAT_1") (pintype "output"))
      (node (ref "R1_BAT") (pin "2") (pinfunction "2_2") (pintype "passive"))
    )
    (net (code "37") (name "PREVGH") (class "Default")
      (node (ref "D5") (pin "1") (pinfunction "K_1") (pintype "bidirectional"))
      (node (ref "EPD_C9") (pin "2") (pinfunction "2_2") (pintype "passive"))
      (node (ref "J1") (pin "21") (pinfunction "21_21") (pintype "bidirectional"))
    )
    (net (code "38") (name "PREVGL") (class "Default")
      (node (ref "D4") (pin "2") (pinfunction "A_2") (pintype "bidirectional"))
      (node (ref "EPD_C11") (pin "2") (pinfunction "2_2") (pintype "passive"))
      (node (ref "J1") (pin "23") (pinfunction "23_23") (pintype "bidirectional"))
    )
    (net (code "39") (name "RESE") (class "Default")
      (node (ref "J1") (pin "3") (pinfunction "3_3") (pintype "bidirectional"))
      (node (ref "Q3") (pin "2") (pinfunction "S_2") (pintype "bidirectional"))
      (node (ref "R3") (pin "2") (pinfunction "2_2") (pintype "passive"))
    )
    (net (code "40") (name "RESE'") (class "Default")
      (node (ref "R2") (pin "2") (pinfunction "2_2") (pintype "passive"))
      (node (ref "R3") (pin "1") (pinfunction "1_1") (pintype "passive"))
      (node (ref "SJ1") (pin "2") (pinfunction "2_2") (pintype "passive"))
    )
    (net (code "41") (name "RESET") (class "Default")
      (node (ref "C5") (pin "1") (pinfunction "1_1") (pintype "passive"))
      (node (ref "IC1") (pin "1") (pinfunction "VOUT_1") (pintype "bidirectional"))
      (node (ref "RESET_BUTTON") (pin "3") (pinfunction "3_3") (pintype "passive"))
      (node (ref "RESET_BUTTON") (pin "4") (pinfunction "4_4") (pintype "passive"))
      (node (ref "R_RESET") (pin "1") (pinfunction "1_1") (pintype "passive"))
      (node (ref "U2") (pin "3") (pinfunction "EN_3") (pintype "input"))
    )
    (net (code "42") (name "RTC_RST") (class "Default")
      (node (ref "U2") (pin "16") (pinfunction "IO18_16") (pintype "bidirectional"))
      (node (ref "U3") (pin "4") (pinfunction "~{RST}_4") (pintype "input"))
    )
    (net (code "43") (name "RX") (class "Default")
      (node (ref "TPRX") (pin "TP") (pinfunction "TP_TP") (pintype "input"))
      (node (ref "U2") (pin "24") (pinfunction "RXD0/GPIO17_24") (pintype "bidirectional"))
    )
    (net (code "44") (name "SCK") (class "Default")
      (node (ref "D9") (pin "2") (pinfunction "2_2") (pintype "passive"))
      (node (ref "J1") (pin "13") (pinfunction "13_13") (pintype "bidirectional"))
      (node (ref "J4") (pin "P5") (pinfunction "CLK_P5") (pintype "bidirectional"))
      (node (ref "R7") (pin "1") (pinfunction "1_1") (pintype "passive"))
      (node (ref "TPSCK") (pin "TP") (pinfunction "TP_TP") (pintype "input"))
      (node (ref "U1") (pin "6") (pinfunction "CLK_6") (pintype "input"))
      (node (ref "U2") (pin "6") (pinfunction "IO6_6") (pintype "bidirectional"))
    )
    (net (code "45") (name "SCL") (class "Default")
      (node (ref "J3") (pin "4") (pinfunction "4_4") (pintype "passive"))
      (node (ref "R2_PINH") (pin "1") (pinfunction "1_1") (pintype "passive"))
      (node (ref "SENSOR2") (pin "4") (pinfunction "SCK_4") (pintype "input"))
      (node (ref "U2") (pin "20") (pinfunction "IO22_20") (pintype "bidirectional"))
      (node (ref "U3") (pin "16") (pinfunction "SCL_16") (pintype "input"))
      (node (ref "U4") (pin "7") (pinfunction "SCL_7") (pintype "input"))
    )
    (net (code "46") (name "SDA") (class "Default")
      (node (ref "J3") (pin "3") (pinfunction "3_3") (pintype "passive"))
      (node (ref "R1_PINH") (pin "1") (pinfunction "1_1") (pintype "passive"))
      (node (ref "SENSOR2") (pin "3") (pinfunction "SDI_3") (pintype "bidirectional"))
      (node (ref "U2") (pin "19") (pinfunction "IO21_19") (pintype "bidirectional"))
      (node (ref "U3") (pin "15") (pinfunction "SDA_15") (pintype "bidirectional"))
      (node (ref "U4") (pin "8") (pinfunction "SDA_8") (pintype "bidirectional"))
    )
    (net (code "47") (name "SRC") (class "Default")
      (node (ref "C4") (pin "2") (pinfunction "2_2") (pintype "passive"))
      (node (ref "D5") (pin "2") (pinfunction "A_2") (pintype "bidirectional"))
      (node (ref "L1") (pin "2") (pinfunction "2_2") (pintype "passive"))
      (node (ref "Q3") (pin "3") (pinfunction "D_3") (pintype "bidirectional"))
    )
    (net (code "48") (name "SS_SD") (class "Default")
      (node (ref "D12") (pin "2") (pinfunction "2_2") (pintype "passive"))
      (node (ref "J4") (pin "P2") (pinfunction "CD/DAT3_P2") (pintype "bidirectional"))
      (node (ref "R10") (pin "1") (pinfunction "1_1") (pintype "passive"))
      (node (ref "U2") (pin "4") (pinfunction "IO4_4") (pintype "bidirectional"))
    )
    (net (code "49") (name "TX") (class "Default")
      (node (ref "TPTX") (pin "TP") (pinfunction "TP_TP") (pintype "input"))
      (node (ref "U2") (pin "25") (pinfunction "TXD0/GPIO16_25") (pintype "bidirectional"))
    )
    (net (code "50") (name "USB_D+") (class "Default")
      (node (ref "D1") (pin "1") (pinfunction "I/O1_1_1") (pintype "bidirectional"))
      (node (ref "U2") (pin "14") (pinfunction "IO13_14") (pintype "bidirectional"))
    )
    (net (code "51") (name "USB_D-") (class "Default")
      (node (ref "D1") (pin "3") (pinfunction "I/O2_1_3") (pintype "bidirectional"))
      (node (ref "U2") (pin "13") (pinfunction "IO12_13") (pintype "bidirectional"))
    )
    (net (code "52") (name "VBAT") (class "Default")
      (node (ref "C2_BAT") (pin "1") (pinfunction "1_1") (pintype "passive"))
      (node (ref "MCP73831") (pin "3") (pinfunction "VBAT_3") (pintype "power_in"))
      (node (ref "Q1") (pin "3") (pinfunction "D_3") (pintype "bidirectional"))
      (node (ref "TPVBAT") (pin "TP") (pinfunction "TP_TP") (pintype "input"))
      (node (ref "U4") (pin "2") (pinfunction "CELL_2") (pintype "power_in"))
      (node (ref "U4") (pin "3") (pinfunction "VDD_3") (pintype "power_in"))
    )
    (net (code "53") (name "VBUS") (class "Default")
      (node (ref "C1_BAT") (pin "1") (pinfunction "1_1") (pintype "passive"))
      (node (ref "C4_USB") (pin "1") (pinfunction "1_1") (pintype "passive"))
      (node (ref "C5_USB") (pin "1") (pinfunction "1_1") (pintype "passive"))
      (node (ref "CHG_LED") (pin "A") (pinfunction "A_A") (pintype "passive"))
      (node (ref "D1") (pin "5") (pinfunction "VBUS_5") (pintype "bidirectional"))
      (node (ref "D2") (pin "2") (pinfunction "ANODE_2") (pintype "bidirectional"))
      (node (ref "MCP73831") (pin "4") (pinfunction "VIN_4") (pintype "power_in"))
      (node (ref "PFMF.050.1") (pin "2") (pinfunction "2_2") (pintype "passive"))
      (node (ref "Q1") (pin "1") (pinfunction "G_1") (pintype "bidirectional"))
      (node (ref "R1_PWRUSB") (pin "2") (pinfunction "2_2") (pintype "passive"))
      (node (ref "TPVBUS") (pin "TP") (pinfunction "TP_TP") (pintype "input"))
    )
    (net (code "54") (name "VRTC") (class "Default")
      (node (ref "C11") (pin "1") (pinfunction "1_1") (pintype "passive"))
      (node (ref "C8") (pin "1") (pinfunction "1_1") (pintype "passive"))
      (node (ref "R_CAPACITOR") (pin "2") (pinfunction "2_2") (pintype "passive"))
      (node (ref "U3") (pin "14") (pinfunction "VBAT_14") (pintype "power_in"))
    )
    (net (code "55") (name "VUSB") (class "Default")
      (node (ref "J2") (pin "A4") (pinfunction "A4_A4") (pintype "bidirectional"))
      (node (ref "J2") (pin "A9") (pinfunction "A9_A9") (pintype "bidirectional"))
      (node (ref "J2") (pin "B4") (pinfunction "B4_B4") (pintype "bidirectional"))
      (node (ref "J2") (pin "B9") (pinfunction "B9_B9") (pintype "bidirectional"))
      (node (ref "PFMF.050.1") (pin "1") (pinfunction "1_1") (pintype "passive"))
    )
    (net (code "56") (name "unconnected-(IC1-NC-Pad4)") (class "Default")
      (node (ref "IC1") (pin "4") (pinfunction "NC_4") (pintype "no_connect"))
    )
    (net (code "57") (name "unconnected-(IC4-NC-Pad4)") (class "Default")
      (node (ref "IC4") (pin "4") (pinfunction "NC_4") (pintype "no_connect"))
    )
    (net (code "58") (name "unconnected-(J1-Pad1)") (class "Default")
      (node (ref "J1") (pin "1") (pinfunction "1_1") (pintype "bidirectional"))
    )
    (net (code "59") (name "unconnected-(J1-Pad6)") (class "Default")
      (node (ref "J1") (pin "6") (pinfunction "6_6") (pintype "bidirectional"))
    )
    (net (code "60") (name "unconnected-(J1-Pad7)") (class "Default")
      (node (ref "J1") (pin "7") (pinfunction "7_7") (pintype "bidirectional"))
    )
    (net (code "61") (name "unconnected-(J2-PadA8)") (class "Default")
      (node (ref "J2") (pin "A8") (pinfunction "A8_A8") (pintype "bidirectional"))
    )
    (net (code "62") (name "unconnected-(J2-PadB8)") (class "Default")
      (node (ref "J2") (pin "B8") (pinfunction "B8_B8") (pintype "bidirectional"))
    )
    (net (code "63") (name "unconnected-(J4-DAT1-PadP8)") (class "Default")
      (node (ref "J4") (pin "P8") (pinfunction "DAT1_P8") (pintype "bidirectional"))
    )
    (net (code "64") (name "unconnected-(J4-DAT2-PadP1)") (class "Default")
      (node (ref "J4") (pin "P1") (pinfunction "DAT2_P1") (pintype "bidirectional"))
    )
    (net (code "65") (name "unconnected-(J4-DETECTION_1-PadS1)") (class "Default")
      (node (ref "J4") (pin "S1") (pinfunction "DETECTION_1_S1") (pintype "bidirectional"))
    )
    (net (code "66") (name "unconnected-(J4-DETECTION_2-PadS2)") (class "Default")
      (node (ref "J4") (pin "S2") (pinfunction "DETECTION_2_S2") (pintype "bidirectional"))
    )
    (net (code "67") (name "unconnected-(U2-NC-Pad22)") (class "Default")
      (node (ref "U2") (pin "22") (pinfunction "NC_22") (pintype "no_connect"))
    )
    (net (code "68") (name "unconnected-(U4-~{ALERT}-Pad5)") (class "Default")
      (node (ref "U4") (pin "5") (pinfunction "~{ALERT}_5") (pintype "output"))
    )
  )
)
